# NEO-M8T_GNSS_FeatherWing.net
KiCad netlist of a schematic drawn in EAGLE
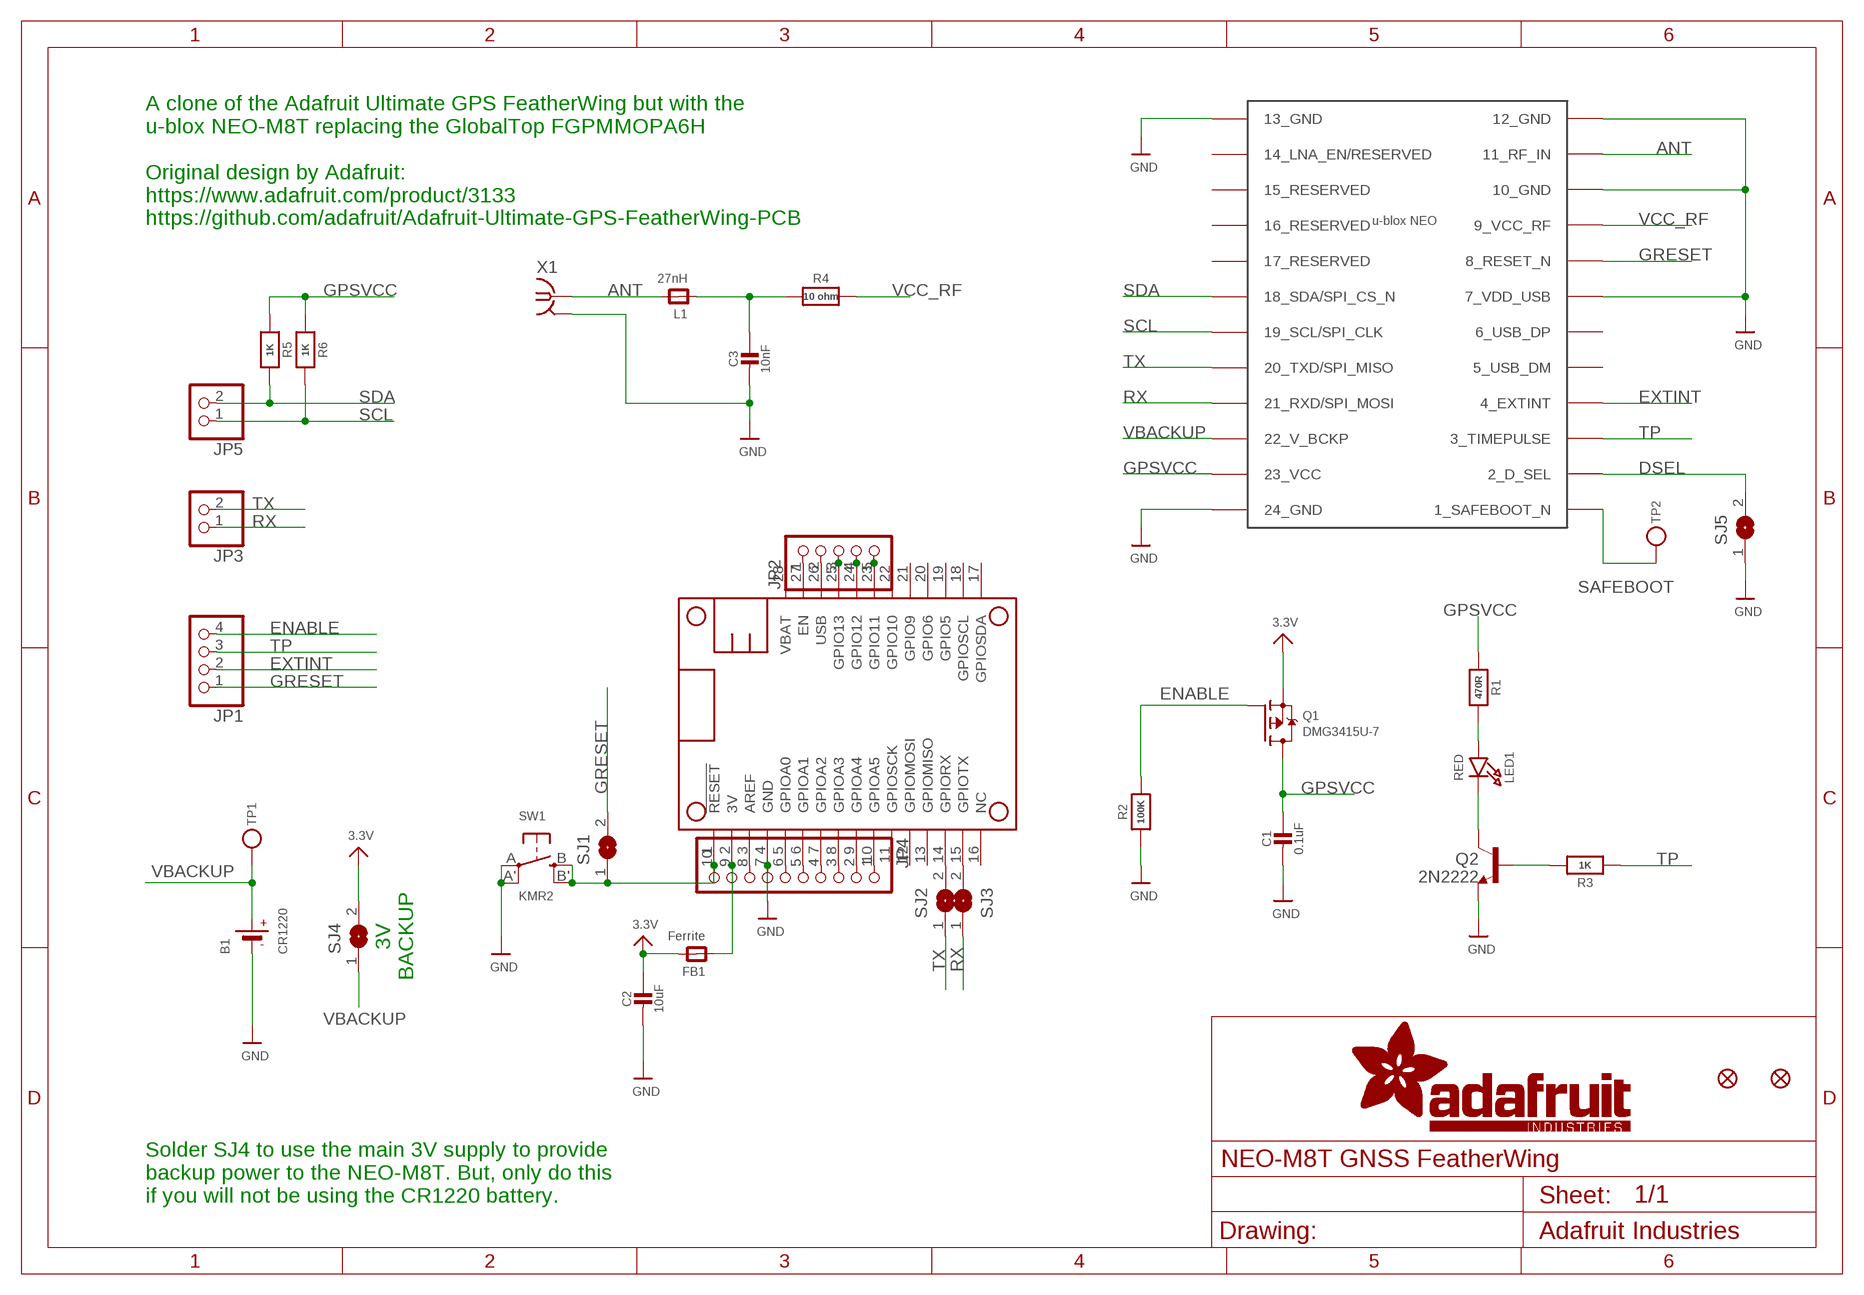
[diagram p0: schematic, sheet 1]

(export (version "E")
  (design (tool "Eeschema 10.0.6"))
  (components
    (comp (ref "B1")
      (value "CR1220")
      (footprint "eagle-import:CR1220-2")
      (libsource (lib "eagle-import") (part "BATTERYCR1220_2"))
    )
    (comp (ref "C1")
      (value "0.1uF")
      (footprint "eagle-import:0805-NO")
      (libsource (lib "eagle-import") (part "CAP_CERAMIC0805-NOOUTLINE"))
    )
    (comp (ref "C2")
      (value "10uF")
      (footprint "eagle-import:0805-NO")
      (libsource (lib "eagle-import") (part "CAP_CERAMIC0805-NOOUTLINE"))
    )
    (comp (ref "C3")
      (value "10nF")
      (footprint "eagle-import:0805-NO")
      (libsource (lib "eagle-import") (part "CAP_CERAMIC0805-NOOUTLINE"))
    )
    (comp (ref "FB1")
      (value "Ferrite")
      (footprint "eagle-import:0805-NO")
      (libsource (lib "eagle-import") (part "FERRITE-0805NO"))
    )
    (comp (ref "FID1")
      (value "FIDUCIAL\"\"")
      (footprint "eagle-import:FIDUCIAL_1MM")
      (libsource (lib "eagle-import") (part "FIDUCIAL{dblquote}{dblquote}"))
    )
    (comp (ref "FID2")
      (value "FIDUCIAL\"\"")
      (footprint "eagle-import:FIDUCIAL_1MM")
      (libsource (lib "eagle-import") (part "FIDUCIAL{dblquote}{dblquote}"))
    )
    (comp (ref "JP1")
      (value "HEADER-1X4ROUND")
      (footprint "eagle-import:1X04_ROUND")
      (libsource (lib "eagle-import") (part "HEADER-1X4ROUND"))
    )
    (comp (ref "JP2")
      (value "HEADER-1X570MIL")
      (footprint "eagle-import:1X05_ROUND_70")
      (libsource (lib "eagle-import") (part "HEADER-1X570MIL"))
    )
    (comp (ref "JP3")
      (value "HEADER-1X2ROUND")
      (footprint "eagle-import:1X02_ROUND")
      (libsource (lib "eagle-import") (part "HEADER-1X2ROUND"))
    )
    (comp (ref "JP4")
      (value "HEADER-1X10ROUND")
      (footprint "eagle-import:1X10_ROUND")
      (libsource (lib "eagle-import") (part "HEADER-1X10ROUND"))
    )
    (comp (ref "JP5")
      (value "HEADER-1X2ROUND")
      (footprint "eagle-import:1X02_ROUND")
      (libsource (lib "eagle-import") (part "HEADER-1X2ROUND"))
    )
    (comp (ref "L1")
      (value "27nH")
      (footprint "eagle-import:0805-NO")
      (libsource (lib "eagle-import") (part "FERRITE-0805NO"))
    )
    (comp (ref "LED1")
      (value "RED")
      (footprint "eagle-import:CHIPLED_0805_NOOUTLINE")
      (libsource (lib "eagle-import") (part "LED0805_NOOUTLINE"))
    )
    (comp (ref "MS1")
      (value "MICROBUILDER_FEATHERWINGSMA")
      (footprint "eagle-import:MICROBUILDER_FEATHERWING_SMA")
      (libsource (lib "eagle-import") (part "MICROBUILDER_FEATHERWINGSMA"))
    )
    (comp (ref "Q1")
      (value "DMG3415U-7")
      (footprint "eagle-import:SOT23-WIDE")
      (libsource (lib "eagle-import") (part "MOSFET-PWIDE"))
    )
    (comp (ref "Q2")
      (value "2N2222")
      (footprint "eagle-import:SOT23-BEC")
      (libsource (lib "eagle-import") (part "-NPN-SOT23-BECMMBT2222ALT1"))
    )
    (comp (ref "R1")
      (value "470R")
      (footprint "eagle-import:0603-NO")
      (libsource (lib "eagle-import") (part "RESISTOR_0603_NOOUT"))
    )
    (comp (ref "R2")
      (value "100K")
      (footprint "eagle-import:0805-NO")
      (libsource (lib "eagle-import") (part "RESISTOR0805_NOOUTLINE"))
    )
    (comp (ref "R3")
      (value "1K")
      (footprint "eagle-import:0603-NO")
      (libsource (lib "eagle-import") (part "RESISTOR_0603_NOOUT"))
    )
    (comp (ref "R4")
      (value "10 ohm")
      (footprint "eagle-import:0805-NO")
      (libsource (lib "eagle-import") (part "RESISTOR0805_NOOUTLINE"))
    )
    (comp (ref "R5")
      (value "1K")
      (footprint "eagle-import:0603-NO")
      (libsource (lib "eagle-import") (part "RESISTOR_0603_NOOUT"))
    )
    (comp (ref "R6")
      (value "1K")
      (footprint "eagle-import:0603-NO")
      (libsource (lib "eagle-import") (part "RESISTOR_0603_NOOUT"))
    )
    (comp (ref "SJ1")
      (value "SOLDERJUMPER")
      (footprint "eagle-import:SOLDERJUMPER_ARROW_NOPASTE")
      (libsource (lib "eagle-import") (part "SOLDERJUMPER"))
    )
    (comp (ref "SJ2")
      (value "SOLDERJUMPERCLOSED")
      (footprint "eagle-import:SOLDERJUMPER_CLOSEDWIRE")
      (libsource (lib "eagle-import") (part "SOLDERJUMPERCLOSED"))
    )
    (comp (ref "SJ3")
      (value "SOLDERJUMPERCLOSED")
      (footprint "eagle-import:SOLDERJUMPER_CLOSEDWIRE")
      (libsource (lib "eagle-import") (part "SOLDERJUMPERCLOSED"))
    )
    (comp (ref "SJ4")
      (value "SOLDERJUMPER")
      (footprint "eagle-import:SOLDERJUMPER_ARROW_NOPASTE")
      (libsource (lib "eagle-import") (part "SOLDERJUMPER"))
    )
    (comp (ref "SJ5")
      (value "SOLDERJUMPER")
      (footprint "eagle-import:SOLDERJUMPER_ARROW_NOPASTE")
      (libsource (lib "eagle-import") (part "SOLDERJUMPER"))
    )
    (comp (ref "SW1")
      (value "KMR2")
      (footprint "eagle-import:BTN_KMR2_4.6X2.8")
      (libsource (lib "eagle-import") (part "SWITCH_TACT_SMT4.6X2.8"))
    )
    (comp (ref "TP1")
      (value "TESTPOINTROUND1.5MM")
      (footprint "eagle-import:TESTPOINT_ROUND_1.5MM")
      (libsource (lib "eagle-import") (part "TESTPOINTROUND1.5MM"))
    )
    (comp (ref "TP2")
      (value "TESTPOINTROUND1.5MM")
      (footprint "eagle-import:TESTPOINT_ROUND_1.5MM")
      (libsource (lib "eagle-import") (part "TESTPOINTROUND1.5MM"))
    )
    (comp (ref "U1")
      (value "NEO-M8")
      (footprint "eagle-import:NEO-M8")
      (libsource (lib "eagle-import") (part "NEO-M8"))
    )
    (comp (ref "X1")
      (value "SMA-142-0711-821/826")
      (footprint "eagle-import:J502-ND-142-0711-821_826")
      (fields (field (name "MF") "JOHNSON COMPONENTS") (field (name "MPN") "142-0711-821"))
      (libsource (lib "eagle-import") (part "SMA-142-0711-821/826"))
    )
  )
  (nets
    (net (code "1") (name "/ANT") (class "Default")
      (node (ref "L1") (pin "2") (pinfunction "P$2_2") (pintype "passive"))
      (node (ref "U1") (pin "11") (pinfunction "11_RF_IN_11") (pintype "bidirectional"))
      (node (ref "X1") (pin "1") (pinfunction "1_1") (pintype "passive"))
    )
    (net (code "2") (name "/DSEL") (class "Default")
      (node (ref "SJ5") (pin "2") (pinfunction "2_2") (pintype "passive"))
      (node (ref "U1") (pin "2") (pinfunction "2_D_SEL_2") (pintype "bidirectional"))
    )
    (net (code "3") (name "/ENABLE") (class "Default")
      (node (ref "JP1") (pin "4") (pinfunction "4_4") (pintype "passive"))
      (node (ref "Q1") (pin "1") (pinfunction "G_1") (pintype "passive"))
      (node (ref "R2") (pin "2") (pinfunction "2_2") (pintype "passive"))
    )
    (net (code "4") (name "/EXTINT") (class "Default")
      (node (ref "JP1") (pin "2") (pinfunction "2_2") (pintype "passive"))
      (node (ref "U1") (pin "4") (pinfunction "4_EXTINT_4") (pintype "bidirectional"))
    )
    (net (code "5") (name "/GPSVCC") (class "Default")
      (node (ref "C1") (pin "1") (pinfunction "1_1") (pintype "passive"))
      (node (ref "Q1") (pin "3") (pinfunction "D_3") (pintype "passive"))
      (node (ref "R1") (pin "1") (pinfunction "1_1") (pintype "passive"))
      (node (ref "R5") (pin "1") (pinfunction "1_1") (pintype "passive"))
      (node (ref "R6") (pin "1") (pinfunction "1_1") (pintype "passive"))
      (node (ref "U1") (pin "23") (pinfunction "23_VCC_23") (pintype "bidirectional"))
    )
    (net (code "6") (name "/GRESET") (class "Default")
      (node (ref "JP1") (pin "1") (pinfunction "1_1") (pintype "passive"))
      (node (ref "SJ1") (pin "2") (pinfunction "2_2") (pintype "passive"))
      (node (ref "U1") (pin "8") (pinfunction "8_RESET_N_8") (pintype "bidirectional"))
    )
    (net (code "7") (name "/RX") (class "Default")
      (node (ref "JP3") (pin "1") (pinfunction "1_1") (pintype "passive"))
      (node (ref "SJ3") (pin "1") (pinfunction "1_1") (pintype "passive"))
      (node (ref "U1") (pin "21") (pinfunction "21_RXD/SPI_MOSI_21") (pintype "bidirectional"))
    )
    (net (code "8") (name "/SAFEBOOT") (class "Default")
      (node (ref "TP2") (pin "P$1") (pinfunction "P$1_P$1") (pintype "bidirectional"))
      (node (ref "U1") (pin "1") (pinfunction "1_SAFEBOOT_N_1") (pintype "bidirectional"))
    )
    (net (code "9") (name "/SCL") (class "Default")
      (node (ref "JP5") (pin "1") (pinfunction "1_1") (pintype "passive"))
      (node (ref "R6") (pin "2") (pinfunction "2_2") (pintype "passive"))
      (node (ref "U1") (pin "19") (pinfunction "19_SCL/SPI_CLK_19") (pintype "bidirectional"))
    )
    (net (code "10") (name "/SDA") (class "Default")
      (node (ref "JP5") (pin "2") (pinfunction "2_2") (pintype "passive"))
      (node (ref "R5") (pin "2") (pinfunction "2_2") (pintype "passive"))
      (node (ref "U1") (pin "18") (pinfunction "18_SDA/SPI_CS_N_18") (pintype "bidirectional"))
    )
    (net (code "11") (name "/TP") (class "Default")
      (node (ref "JP1") (pin "3") (pinfunction "3_3") (pintype "passive"))
      (node (ref "R3") (pin "1") (pinfunction "1_1") (pintype "passive"))
      (node (ref "U1") (pin "3") (pinfunction "3_TIMEPULSE_3") (pintype "bidirectional"))
    )
    (net (code "12") (name "/TX") (class "Default")
      (node (ref "JP3") (pin "2") (pinfunction "2_2") (pintype "passive"))
      (node (ref "SJ2") (pin "1") (pinfunction "1_1") (pintype "passive"))
      (node (ref "U1") (pin "20") (pinfunction "20_TXD/SPI_MISO_20") (pintype "bidirectional"))
    )
    (net (code "13") (name "/VBACKUP") (class "Default")
      (node (ref "B1") (pin "+") (pinfunction "+_+") (pintype "passive"))
      (node (ref "SJ4") (pin "1") (pinfunction "1_1") (pintype "passive"))
      (node (ref "TP1") (pin "P$1") (pinfunction "P$1_P$1") (pintype "bidirectional"))
      (node (ref "U1") (pin "22") (pinfunction "22_V_BCKP_22") (pintype "bidirectional"))
    )
    (net (code "14") (name "/VBAT") (class "Default")
      (node (ref "MS1") (pin "28") (pinfunction "VBAT_28") (pintype "power_in"))
    )
    (net (code "15") (name "/VCC_RF") (class "Default")
      (node (ref "R4") (pin "2") (pinfunction "2_2") (pintype "passive"))
      (node (ref "U1") (pin "9") (pinfunction "9_VCC_RF_9") (pintype "bidirectional"))
    )
    (net (code "16") (name "3.3V") (class "Default")
      (node (ref "C2") (pin "1") (pinfunction "1_1") (pintype "passive"))
      (node (ref "FB1") (pin "2") (pinfunction "P$2_2") (pintype "passive"))
      (node (ref "Q1") (pin "2") (pinfunction "S_2") (pintype "passive"))
      (node (ref "SJ4") (pin "2") (pinfunction "2_2") (pintype "passive"))
    )
    (net (code "17") (name "GND") (class "Default")
      (node (ref "B1") (pin "-") (pinfunction "-_-") (pintype "passive"))
      (node (ref "C1") (pin "2") (pinfunction "2_2") (pintype "passive"))
      (node (ref "C2") (pin "2") (pinfunction "2_2") (pintype "passive"))
      (node (ref "C3") (pin "2") (pinfunction "2_2") (pintype "passive"))
      (node (ref "JP4") (pin "7") (pinfunction "7_7") (pintype "passive"))
      (node (ref "MS1") (pin "4") (pinfunction "GND_4") (pintype "power_in"))
      (node (ref "Q2") (pin "E") (pinfunction "E_E") (pintype "passive"))
      (node (ref "R2") (pin "1") (pinfunction "1_1") (pintype "passive"))
      (node (ref "SJ5") (pin "1") (pinfunction "1_1") (pintype "passive"))
      (node (ref "SW1") (pin "A") (pinfunction "P_A") (pintype "passive"))
      (node (ref "SW1") (pin "A'") (pinfunction "P1_A'") (pintype "passive"))
      (node (ref "U1") (pin "10") (pinfunction "10_GND_10") (pintype "bidirectional"))
      (node (ref "U1") (pin "12") (pinfunction "12_GND_12") (pintype "bidirectional"))
      (node (ref "U1") (pin "13") (pinfunction "13_GND_13") (pintype "bidirectional"))
      (node (ref "U1") (pin "24") (pinfunction "24_GND_24") (pintype "bidirectional"))
      (node (ref "U1") (pin "7") (pinfunction "7_VDD_USB_7") (pintype "bidirectional"))
      (node (ref "X1") (pin "G@1") (pinfunction "2_G@1") (pintype "passive"))
      (node (ref "X1") (pin "G@2") (pinfunction "2_G@2") (pintype "passive"))
      (node (ref "X1") (pin "G@3") (pinfunction "2_G@3") (pintype "passive"))
      (node (ref "X1") (pin "G@4") (pinfunction "2_G@4") (pintype "passive"))
    )
    (net (code "18") (name "Net-(FB1-P$1)") (class "Default")
      (node (ref "FB1") (pin "1") (pinfunction "P$1_1") (pintype "passive"))
      (node (ref "JP4") (pin "9") (pinfunction "9_9") (pintype "passive"))
      (node (ref "MS1") (pin "2") (pinfunction "3V_2") (pintype "power_in"))
    )
    (net (code "19") (name "Net-(L1-P$1)") (class "Default")
      (node (ref "C3") (pin "1") (pinfunction "1_1") (pintype "passive"))
      (node (ref "L1") (pin "1") (pinfunction "P$1_1") (pintype "passive"))
      (node (ref "R4") (pin "1") (pinfunction "1_1") (pintype "passive"))
    )
    (net (code "20") (name "Net-(LED1-PadA)") (class "Default")
      (node (ref "LED1") (pin "A") (pinfunction "A_A") (pintype "passive"))
      (node (ref "R1") (pin "2") (pinfunction "2_2") (pintype "passive"))
    )
    (net (code "21") (name "Net-(LED1-PadC)") (class "Default")
      (node (ref "LED1") (pin "C") (pinfunction "C_C") (pintype "passive"))
      (node (ref "Q2") (pin "C") (pinfunction "C_C") (pintype "passive"))
    )
    (net (code "22") (name "Net-(MS1-AREF)") (class "Default")
      (node (ref "JP4") (pin "8") (pinfunction "8_8") (pintype "passive"))
      (node (ref "MS1") (pin "3") (pinfunction "AREF_3") (pintype "passive"))
    )
    (net (code "23") (name "Net-(MS1-EN)") (class "Default")
      (node (ref "JP2") (pin "1") (pinfunction "1_1") (pintype "passive"))
      (node (ref "MS1") (pin "27") (pinfunction "EN_27") (pintype "passive"))
    )
    (net (code "24") (name "Net-(MS1-GPIO11)") (class "Default")
      (node (ref "JP2") (pin "5") (pinfunction "5_5") (pintype "passive"))
      (node (ref "MS1") (pin "23") (pinfunction "GPIO11_23") (pintype "bidirectional"))
    )
    (net (code "25") (name "Net-(MS1-GPIO12)") (class "Default")
      (node (ref "JP2") (pin "4") (pinfunction "4_4") (pintype "passive"))
      (node (ref "MS1") (pin "24") (pinfunction "GPIO12_24") (pintype "bidirectional"))
    )
    (net (code "26") (name "Net-(MS1-GPIO13)") (class "Default")
      (node (ref "JP2") (pin "3") (pinfunction "3_3") (pintype "passive"))
      (node (ref "MS1") (pin "25") (pinfunction "GPIO13_25") (pintype "bidirectional"))
    )
    (net (code "27") (name "Net-(MS1-GPIOA0)") (class "Default")
      (node (ref "JP4") (pin "6") (pinfunction "6_6") (pintype "passive"))
      (node (ref "MS1") (pin "5") (pinfunction "GPIOA0_5") (pintype "bidirectional"))
    )
    (net (code "28") (name "Net-(MS1-GPIOA1)") (class "Default")
      (node (ref "JP4") (pin "5") (pinfunction "5_5") (pintype "passive"))
      (node (ref "MS1") (pin "6") (pinfunction "GPIOA1_6") (pintype "bidirectional"))
    )
    (net (code "29") (name "Net-(MS1-GPIOA2)") (class "Default")
      (node (ref "JP4") (pin "4") (pinfunction "4_4") (pintype "passive"))
      (node (ref "MS1") (pin "7") (pinfunction "GPIOA2_7") (pintype "bidirectional"))
    )
    (net (code "30") (name "Net-(MS1-GPIOA3)") (class "Default")
      (node (ref "JP4") (pin "3") (pinfunction "3_3") (pintype "passive"))
      (node (ref "MS1") (pin "8") (pinfunction "GPIOA3_8") (pintype "bidirectional"))
    )
    (net (code "31") (name "Net-(MS1-GPIOA4)") (class "Default")
      (node (ref "JP4") (pin "2") (pinfunction "2_2") (pintype "passive"))
      (node (ref "MS1") (pin "9") (pinfunction "GPIOA4_9") (pintype "bidirectional"))
    )
    (net (code "32") (name "Net-(MS1-GPIOA5)") (class "Default")
      (node (ref "JP4") (pin "1") (pinfunction "1_1") (pintype "passive"))
      (node (ref "MS1") (pin "10") (pinfunction "GPIOA5_10") (pintype "bidirectional"))
    )
    (net (code "33") (name "Net-(MS1-GPIORX)") (class "Default")
      (node (ref "MS1") (pin "14") (pinfunction "GPIORX_14") (pintype "bidirectional"))
      (node (ref "SJ2") (pin "2") (pinfunction "2_2") (pintype "passive"))
    )
    (net (code "34") (name "Net-(MS1-GPIOTX)") (class "Default")
      (node (ref "MS1") (pin "15") (pinfunction "GPIOTX_15") (pintype "bidirectional"))
      (node (ref "SJ3") (pin "2") (pinfunction "2_2") (pintype "passive"))
    )
    (net (code "35") (name "Net-(MS1-USB)") (class "Default")
      (node (ref "JP2") (pin "2") (pinfunction "2_2") (pintype "passive"))
      (node (ref "MS1") (pin "26") (pinfunction "USB_26") (pintype "power_in"))
    )
    (net (code "36") (name "Net-(MS1-~{RESET})") (class "Default")
      (node (ref "JP4") (pin "10") (pinfunction "10_10") (pintype "passive"))
      (node (ref "MS1") (pin "1") (pinfunction "~{RESET}_1") (pintype "input"))
      (node (ref "SJ1") (pin "1") (pinfunction "1_1") (pintype "passive"))
      (node (ref "SW1") (pin "B") (pinfunction "S_B") (pintype "passive"))
      (node (ref "SW1") (pin "B'") (pinfunction "S1_B'") (pintype "passive"))
    )
    (net (code "37") (name "Net-(Q2-PadB)") (class "Default")
      (node (ref "Q2") (pin "B") (pinfunction "B_B") (pintype "passive"))
      (node (ref "R3") (pin "2") (pinfunction "2_2") (pintype "passive"))
    )
    (net (code "38") (name "unconnected-(MS1-GPIO5-Pad19)") (class "Default")
      (node (ref "MS1") (pin "19") (pinfunction "GPIO5_19") (pintype "bidirectional"))
    )
    (net (code "39") (name "unconnected-(MS1-GPIO6-Pad20)") (class "Default")
      (node (ref "MS1") (pin "20") (pinfunction "GPIO6_20") (pintype "bidirectional"))
    )
    (net (code "40") (name "unconnected-(MS1-GPIO9-Pad21)") (class "Default")
      (node (ref "MS1") (pin "21") (pinfunction "GPIO9_21") (pintype "bidirectional"))
    )
    (net (code "41") (name "unconnected-(MS1-GPIO10-Pad22)") (class "Default")
      (node (ref "MS1") (pin "22") (pinfunction "GPIO10_22") (pintype "bidirectional"))
    )
    (net (code "42") (name "unconnected-(MS1-GPIOMISO-Pad13)") (class "Default")
      (node (ref "MS1") (pin "13") (pinfunction "GPIOMISO_13") (pintype "bidirectional"))
    )
    (net (code "43") (name "unconnected-(MS1-GPIOMOSI-Pad12)") (class "Default")
      (node (ref "MS1") (pin "12") (pinfunction "GPIOMOSI_12") (pintype "bidirectional"))
    )
    (net (code "44") (name "unconnected-(MS1-GPIOSCK-Pad11)") (class "Default")
      (node (ref "MS1") (pin "11") (pinfunction "GPIOSCK_11") (pintype "bidirectional"))
    )
    (net (code "45") (name "unconnected-(MS1-GPIOSCL-Pad18)") (class "Default")
      (node (ref "MS1") (pin "18") (pinfunction "GPIOSCL_18") (pintype "bidirectional"))
    )
    (net (code "46") (name "unconnected-(MS1-GPIOSDA-Pad17)") (class "Default")
      (node (ref "MS1") (pin "17") (pinfunction "GPIOSDA_17") (pintype "bidirectional"))
    )
    (net (code "47") (name "unconnected-(MS1-NC-Pad16)") (class "Default")
      (node (ref "MS1") (pin "16") (pinfunction "NC_16") (pintype "passive"))
    )
    (net (code "48") (name "unconnected-(U1-5_USB_DM-Pad5)") (class "Default")
      (node (ref "U1") (pin "5") (pinfunction "5_USB_DM_5") (pintype "bidirectional"))
    )
    (net (code "49") (name "unconnected-(U1-6_USB_DP-Pad6)") (class "Default")
      (node (ref "U1") (pin "6") (pinfunction "6_USB_DP_6") (pintype "bidirectional"))
    )
    (net (code "50") (name "unconnected-(U1-14_LNA_EN{slash}RESERVED-Pad14)") (class "Default")
      (node (ref "U1") (pin "14") (pinfunction "14_LNA_EN/RESERVED_14") (pintype "bidirectional"))
    )
    (net (code "51") (name "unconnected-(U1-15_RESERVED-Pad15)") (class "Default")
      (node (ref "U1") (pin "15") (pinfunction "15_RESERVED_15") (pintype "bidirectional"))
    )
    (net (code "52") (name "unconnected-(U1-16_RESERVED-Pad16)") (class "Default")
      (node (ref "U1") (pin "16") (pinfunction "16_RESERVED_16") (pintype "bidirectional"))
    )
    (net (code "53") (name "unconnected-(U1-17_RESERVED-Pad17)") (class "Default")
      (node (ref "U1") (pin "17") (pinfunction "17_RESERVED_17") (pintype "bidirectional"))
    )
  )
)
